# Display.net
KiCad netlist of a schematic drawn in EAGLE
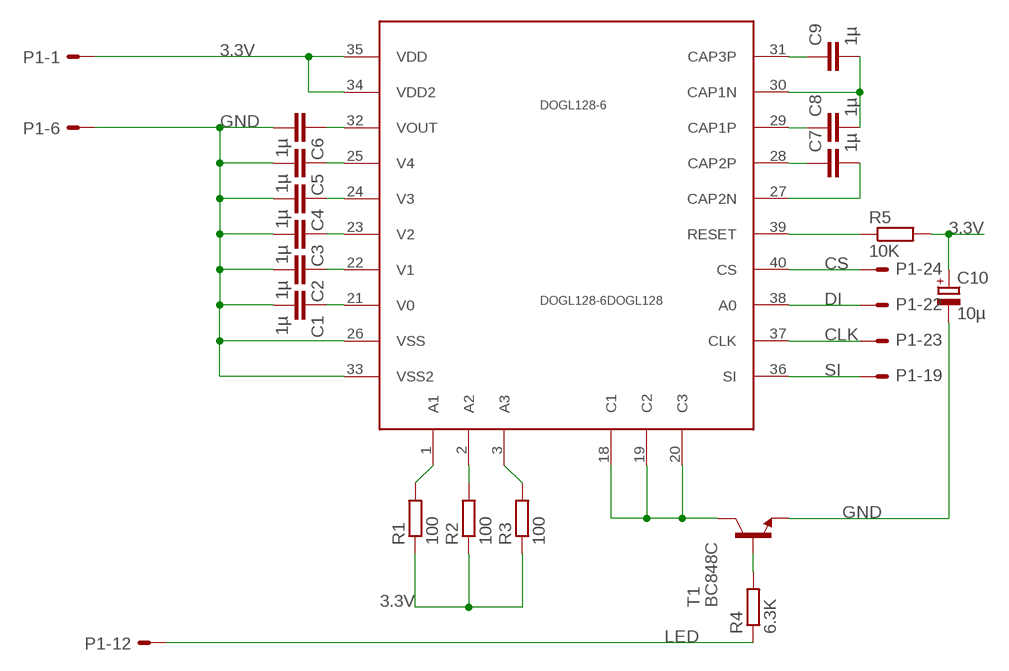
[diagram p0: schematic, sheet 1]

(export (version "E")
  (design (tool "Eeschema 10.0.6"))
  (components
    (comp (ref "C1")
      (value "1µ")
      (footprint "eagle-import:C1206")
      (libsource (lib "eagle-import") (part "C-EUC1206"))
    )
    (comp (ref "C2")
      (value "1µ")
      (footprint "eagle-import:C1206")
      (libsource (lib "eagle-import") (part "C-EUC1206"))
    )
    (comp (ref "C3")
      (value "1µ")
      (footprint "eagle-import:C1206")
      (libsource (lib "eagle-import") (part "C-EUC1206"))
    )
    (comp (ref "C4")
      (value "1µ")
      (footprint "eagle-import:C1206")
      (libsource (lib "eagle-import") (part "C-EUC1206"))
    )
    (comp (ref "C5")
      (value "1µ")
      (footprint "eagle-import:C1206")
      (libsource (lib "eagle-import") (part "C-EUC1206"))
    )
    (comp (ref "C6")
      (value "1µ")
      (footprint "eagle-import:C1206")
      (libsource (lib "eagle-import") (part "C-EUC1206"))
    )
    (comp (ref "C7")
      (value "1µ")
      (footprint "eagle-import:C1206")
      (libsource (lib "eagle-import") (part "C-EUC1206"))
    )
    (comp (ref "C8")
      (value "1µ")
      (footprint "eagle-import:C1206")
      (libsource (lib "eagle-import") (part "C-EUC1206"))
    )
    (comp (ref "C9")
      (value "1µ")
      (footprint "eagle-import:C1206")
      (libsource (lib "eagle-import") (part "C-EUC1206"))
    )
    (comp (ref "C10")
      (value "10µ")
      (footprint "eagle-import:CT6032")
      (libsource (lib "eagle-import") (part "CPOL-EUCT6032"))
    )
    (comp (ref "DOGL128-6")
      (value "DOGL128-6DOGL128")
      (footprint "eagle-import:DOGL128")
      (libsource (lib "eagle-import") (part "DOGL128-6DOGL128"))
    )
    (comp (ref "P1")
      (value "ML26E")
      (footprint "eagle-import:ML26")
      (libsource (lib "eagle-import") (part "ML26E"))
    )
    (comp (ref "R1")
      (value "100")
      (footprint "eagle-import:0207_10")
      (libsource (lib "eagle-import") (part "R-EU_0207/10"))
    )
    (comp (ref "R2")
      (value "100")
      (footprint "eagle-import:0207_10")
      (libsource (lib "eagle-import") (part "R-EU_0207/10"))
    )
    (comp (ref "R3")
      (value "100")
      (footprint "eagle-import:0207_10")
      (libsource (lib "eagle-import") (part "R-EU_0207/10"))
    )
    (comp (ref "R4")
      (value "6.3K")
      (footprint "eagle-import:0207_10")
      (libsource (lib "eagle-import") (part "R-EU_0207/10"))
    )
    (comp (ref "R5")
      (value "10K")
      (footprint "eagle-import:0207_12")
      (libsource (lib "eagle-import") (part "R-EU_0207/12"))
    )
    (comp (ref "T1")
      (value "BC848C")
      (footprint "eagle-import:SOT23-BEC")
      (libsource (lib "eagle-import") (part "-NPN-SOT23-BECBC848C"))
    )
  )
  (nets
    (net (code "1") (name "/3.3V") (class "Default")
      (node (ref "C10") (pin "+") (pinfunction "+_+") (pintype "passive"))
      (node (ref "DOGL128-6") (pin "34") (pinfunction "VDD2_34") (pintype "power_in"))
      (node (ref "DOGL128-6") (pin "35") (pinfunction "VDD_35") (pintype "power_in"))
      (node (ref "P1") (pin "1") (pinfunction "S_1") (pintype "passive"))
      (node (ref "R1") (pin "1") (pinfunction "1_1") (pintype "passive"))
      (node (ref "R2") (pin "1") (pinfunction "1_1") (pintype "passive"))
      (node (ref "R3") (pin "1") (pinfunction "1_1") (pintype "passive"))
      (node (ref "R5") (pin "2") (pinfunction "2_2") (pintype "passive"))
    )
    (net (code "2") (name "/CLK") (class "Default")
      (node (ref "DOGL128-6") (pin "37") (pinfunction "CLK_37") (pintype "input"))
      (node (ref "P1") (pin "23") (pinfunction "S_23") (pintype "passive"))
    )
    (net (code "3") (name "/CS") (class "Default")
      (node (ref "DOGL128-6") (pin "40") (pinfunction "CS_40") (pintype "input"))
      (node (ref "P1") (pin "24") (pinfunction "S_24") (pintype "passive"))
    )
    (net (code "4") (name "/DI") (class "Default")
      (node (ref "DOGL128-6") (pin "38") (pinfunction "A0_38") (pintype "input"))
      (node (ref "P1") (pin "22") (pinfunction "S_22") (pintype "passive"))
    )
    (net (code "5") (name "/GND") (class "Default")
      (node (ref "C1") (pin "2") (pinfunction "2_2") (pintype "passive"))
      (node (ref "C10") (pin "-") (pinfunction "-_-") (pintype "passive"))
      (node (ref "C2") (pin "2") (pinfunction "2_2") (pintype "passive"))
      (node (ref "C3") (pin "2") (pinfunction "2_2") (pintype "passive"))
      (node (ref "C4") (pin "2") (pinfunction "2_2") (pintype "passive"))
      (node (ref "C5") (pin "2") (pinfunction "2_2") (pintype "passive"))
      (node (ref "C6") (pin "2") (pinfunction "2_2") (pintype "passive"))
      (node (ref "DOGL128-6") (pin "26") (pinfunction "VSS_26") (pintype "power_in"))
      (node (ref "DOGL128-6") (pin "33") (pinfunction "VSS2_33") (pintype "power_in"))
      (node (ref "P1") (pin "6") (pinfunction "S_6") (pintype "passive"))
      (node (ref "T1") (pin "E") (pinfunction "E_E") (pintype "passive"))
    )
    (net (code "6") (name "/LED") (class "Default")
      (node (ref "P1") (pin "12") (pinfunction "S_12") (pintype "passive"))
      (node (ref "R4") (pin "1") (pinfunction "1_1") (pintype "passive"))
    )
    (net (code "7") (name "/SI") (class "Default")
      (node (ref "DOGL128-6") (pin "36") (pinfunction "SI_36") (pintype "input"))
      (node (ref "P1") (pin "19") (pinfunction "S_19") (pintype "passive"))
    )
    (net (code "8") (name "Net-(DOGL128-6-A1)") (class "Default")
      (node (ref "DOGL128-6") (pin "1") (pinfunction "A1_1") (pintype "input"))
      (node (ref "R1") (pin "2") (pinfunction "2_2") (pintype "passive"))
    )
    (net (code "9") (name "Net-(DOGL128-6-A2)") (class "Default")
      (node (ref "DOGL128-6") (pin "2") (pinfunction "A2_2") (pintype "input"))
      (node (ref "R2") (pin "2") (pinfunction "2_2") (pintype "passive"))
    )
    (net (code "10") (name "Net-(DOGL128-6-A3)") (class "Default")
      (node (ref "DOGL128-6") (pin "3") (pinfunction "A3_3") (pintype "input"))
      (node (ref "R3") (pin "2") (pinfunction "2_2") (pintype "passive"))
    )
    (net (code "11") (name "Net-(DOGL128-6-C1)") (class "Default")
      (node (ref "DOGL128-6") (pin "18") (pinfunction "C1_18") (pintype "output"))
      (node (ref "DOGL128-6") (pin "19") (pinfunction "C2_19") (pintype "output"))
      (node (ref "DOGL128-6") (pin "20") (pinfunction "C3_20") (pintype "output"))
      (node (ref "T1") (pin "C") (pinfunction "C_C") (pintype "passive"))
    )
    (net (code "12") (name "Net-(DOGL128-6-CAP1N)") (class "Default")
      (node (ref "C8") (pin "2") (pinfunction "2_2") (pintype "passive"))
      (node (ref "C9") (pin "2") (pinfunction "2_2") (pintype "passive"))
      (node (ref "DOGL128-6") (pin "30") (pinfunction "CAP1N_30") (pintype "passive"))
    )
    (net (code "13") (name "Net-(DOGL128-6-CAP1P)") (class "Default")
      (node (ref "C8") (pin "1") (pinfunction "1_1") (pintype "passive"))
      (node (ref "DOGL128-6") (pin "29") (pinfunction "CAP1P_29") (pintype "passive"))
    )
    (net (code "14") (name "Net-(DOGL128-6-CAP2N)") (class "Default")
      (node (ref "C7") (pin "2") (pinfunction "2_2") (pintype "passive"))
      (node (ref "DOGL128-6") (pin "27") (pinfunction "CAP2N_27") (pintype "passive"))
    )
    (net (code "15") (name "Net-(DOGL128-6-CAP2P)") (class "Default")
      (node (ref "C7") (pin "1") (pinfunction "1_1") (pintype "passive"))
      (node (ref "DOGL128-6") (pin "28") (pinfunction "CAP2P_28") (pintype "passive"))
    )
    (net (code "16") (name "Net-(DOGL128-6-CAP3P)") (class "Default")
      (node (ref "C9") (pin "1") (pinfunction "1_1") (pintype "passive"))
      (node (ref "DOGL128-6") (pin "31") (pinfunction "CAP3P_31") (pintype "passive"))
    )
    (net (code "17") (name "Net-(DOGL128-6-RESET)") (class "Default")
      (node (ref "DOGL128-6") (pin "39") (pinfunction "RESET_39") (pintype "input"))
      (node (ref "R5") (pin "1") (pinfunction "1_1") (pintype "passive"))
    )
    (net (code "18") (name "Net-(DOGL128-6-V0)") (class "Default")
      (node (ref "C1") (pin "1") (pinfunction "1_1") (pintype "passive"))
      (node (ref "DOGL128-6") (pin "21") (pinfunction "V0_21") (pintype "passive"))
    )
    (net (code "19") (name "Net-(DOGL128-6-V1)") (class "Default")
      (node (ref "C2") (pin "1") (pinfunction "1_1") (pintype "passive"))
      (node (ref "DOGL128-6") (pin "22") (pinfunction "V1_22") (pintype "passive"))
    )
    (net (code "20") (name "Net-(DOGL128-6-V2)") (class "Default")
      (node (ref "C3") (pin "1") (pinfunction "1_1") (pintype "passive"))
      (node (ref "DOGL128-6") (pin "23") (pinfunction "V2_23") (pintype "passive"))
    )
    (net (code "21") (name "Net-(DOGL128-6-V3)") (class "Default")
      (node (ref "C4") (pin "1") (pinfunction "1_1") (pintype "passive"))
      (node (ref "DOGL128-6") (pin "24") (pinfunction "V3_24") (pintype "passive"))
    )
    (net (code "22") (name "Net-(DOGL128-6-V4)") (class "Default")
      (node (ref "C5") (pin "1") (pinfunction "1_1") (pintype "passive"))
      (node (ref "DOGL128-6") (pin "25") (pinfunction "V4_25") (pintype "passive"))
    )
    (net (code "23") (name "Net-(DOGL128-6-VOUT)") (class "Default")
      (node (ref "C6") (pin "1") (pinfunction "1_1") (pintype "passive"))
      (node (ref "DOGL128-6") (pin "32") (pinfunction "VOUT_32") (pintype "power_in"))
    )
    (net (code "24") (name "Net-(R4-Pad2)") (class "Default")
      (node (ref "R4") (pin "2") (pinfunction "2_2") (pintype "passive"))
      (node (ref "T1") (pin "B") (pinfunction "B_B") (pintype "passive"))
    )
  )
)
